# tetris_fs.net
KiCad netlist of a schematic drawn in EAGLE
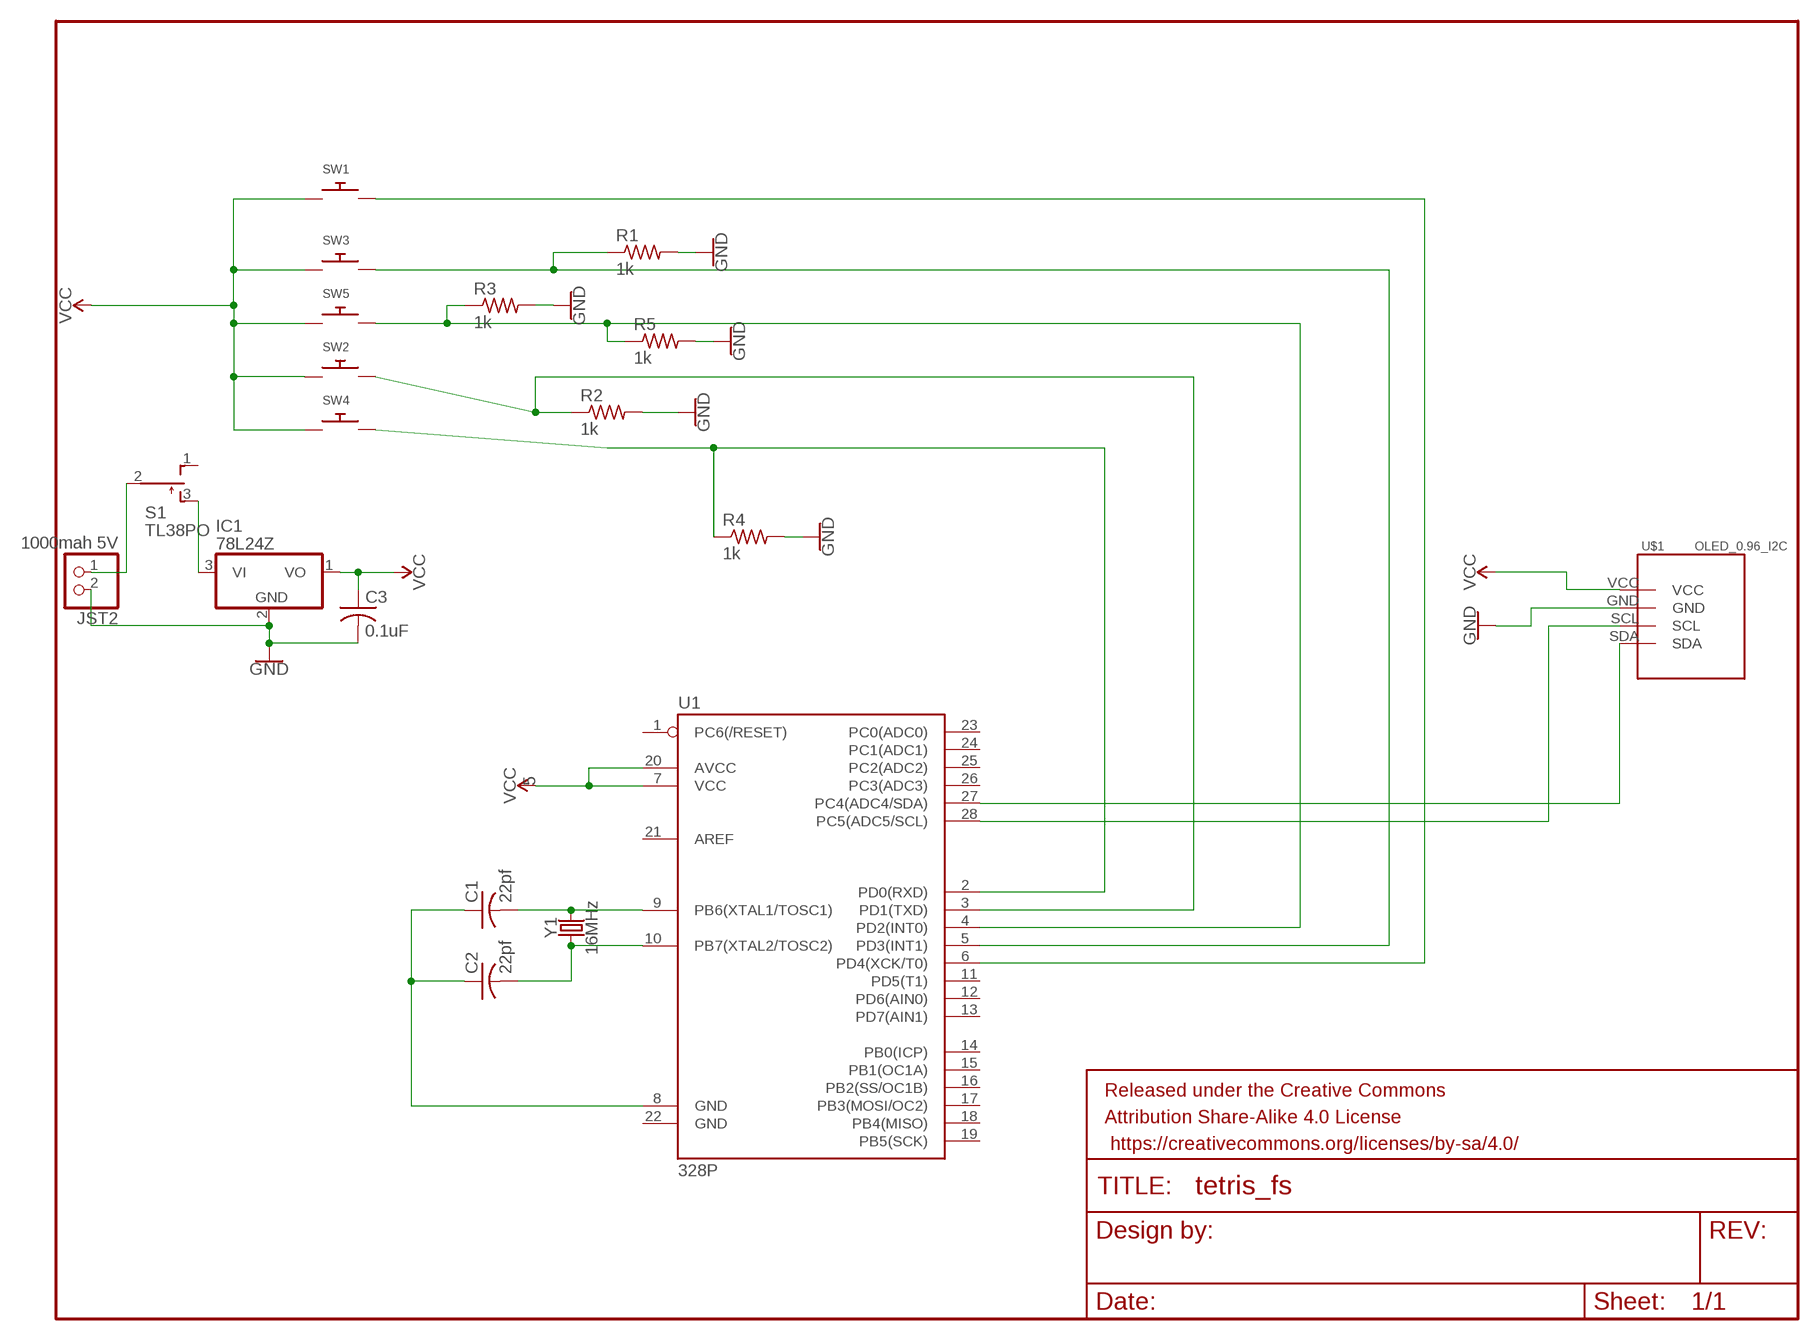
[diagram p0: schematic, sheet 1]

(export (version "E")
  (design (tool "Eeschema 10.0.6"))
  (components
    (comp (ref "C1")
      (value "22pf")
      (footprint "eagle-import:C050-030X075")
      (libsource (lib "eagle-import") (part "C-US050-030X075"))
    )
    (comp (ref "C2")
      (value "22pf")
      (footprint "eagle-import:C050-030X075")
      (libsource (lib "eagle-import") (part "C-US050-030X075"))
    )
    (comp (ref "C3")
      (value "0.1uF")
      (footprint "eagle-import:C050-030X075")
      (libsource (lib "eagle-import") (part "C-US050-030X075"))
    )
    (comp (ref "FRAME1")
      (value "FRAME-LETTERNO_PACKAGE")
      (footprint "eagle-import:DUMMY")
      (fields (field (name "DESIGNER") "Nobody"))
      (libsource (lib "eagle-import") (part "FRAME-LETTERNO_PACKAGE"))
    )
    (comp (ref "IC1")
      (value "78L24Z")
      (footprint "eagle-import:TO92")
      (libsource (lib "eagle-import") (part "78ZL24"))
    )
    (comp (ref "JST2")
      (value "1000mah 5V")
      (footprint "eagle-import:JST-PH-2-SMT-RA")
      (libsource (lib "eagle-import") (part "JST_2PIN-SMT-RA"))
    )
    (comp (ref "R1")
      (value "1k")
      (footprint "eagle-import:0805-THM")
      (libsource (lib "eagle-import") (part "R-US_FLIPFLOP"))
    )
    (comp (ref "R2")
      (value "1k")
      (footprint "eagle-import:0805-THM")
      (libsource (lib "eagle-import") (part "R-US_FLIPFLOP"))
    )
    (comp (ref "R3")
      (value "1k")
      (footprint "eagle-import:0805-THM")
      (libsource (lib "eagle-import") (part "R-US_FLIPFLOP"))
    )
    (comp (ref "R4")
      (value "1k")
      (footprint "eagle-import:0805-THM")
      (libsource (lib "eagle-import") (part "R-US_FLIPFLOP"))
    )
    (comp (ref "R5")
      (value "1k")
      (footprint "eagle-import:0805-THM")
      (libsource (lib "eagle-import") (part "R-US_FLIPFLOP"))
    )
    (comp (ref "S1")
      (value "TL38PO")
      (footprint "eagle-import:TL3XPO")
      (libsource (lib "eagle-import") (part "TL38PO"))
    )
    (comp (ref "SW1")
      (value "SWITCH_PUSHBUTTONC&K_KSS")
      (footprint "eagle-import:BTN_CK_KSS")
      (libsource (lib "eagle-import") (part "SWITCH_PUSHBUTTONC&K_KSS"))
    )
    (comp (ref "SW2")
      (value "SWITCH_PUSHBUTTONC&K_KSS")
      (footprint "eagle-import:BTN_CK_KSS")
      (libsource (lib "eagle-import") (part "SWITCH_PUSHBUTTONC&K_KSS"))
    )
    (comp (ref "SW3")
      (value "SWITCH_PUSHBUTTONC&K_KSS")
      (footprint "eagle-import:BTN_CK_KSS")
      (libsource (lib "eagle-import") (part "SWITCH_PUSHBUTTONC&K_KSS"))
    )
    (comp (ref "SW4")
      (value "SWITCH_PUSHBUTTONC&K_KSS")
      (footprint "eagle-import:BTN_CK_KSS")
      (libsource (lib "eagle-import") (part "SWITCH_PUSHBUTTONC&K_KSS"))
    )
    (comp (ref "SW5")
      (value "SWITCH_PUSHBUTTONC&K_KSS")
      (footprint "eagle-import:BTN_CK_KSS")
      (libsource (lib "eagle-import") (part "SWITCH_PUSHBUTTONC&K_KSS"))
    )
    (comp (ref "U$1")
      (value "OLED_0.96_I2C")
      (footprint "eagle-import:OLED_0.96_I2C")
      (libsource (lib "eagle-import") (part "OLED_0.96_I2C"))
    )
    (comp (ref "U1")
      (value "328P")
      (footprint "eagle-import:DIP28")
      (libsource (lib "eagle-import") (part "ATMEGA328P_PDIP"))
    )
    (comp (ref "Y1")
      (value "16MHz")
      (footprint "eagle-import:HC49US")
      (libsource (lib "eagle-import") (part "CRYSTAL-16MHZPTH-HC49US"))
    )
  )
  (nets
    (net (code "1") (name "GND") (class "Default")
      (node (ref "C3") (pin "2") (pinfunction "2_2") (pintype "passive"))
      (node (ref "IC1") (pin "2") (pinfunction "GND_2") (pintype "passive"))
      (node (ref "JST2") (pin "2") (pinfunction "1_2") (pintype "passive"))
      (node (ref "R1") (pin "2") (pinfunction "2_2") (pintype "passive"))
      (node (ref "R2") (pin "2") (pinfunction "2_2") (pintype "passive"))
      (node (ref "R3") (pin "2") (pinfunction "2_2") (pintype "passive"))
      (node (ref "R4") (pin "2") (pinfunction "2_2") (pintype "passive"))
      (node (ref "R5") (pin "2") (pinfunction "2_2") (pintype "passive"))
      (node (ref "U$1") (pin "GND") (pinfunction "GND_GND") (pintype "bidirectional"))
    )
    (net (code "2") (name "Net-(C1-Pad1)") (class "Default")
      (node (ref "C1") (pin "1") (pinfunction "1_1") (pintype "passive"))
      (node (ref "C2") (pin "1") (pinfunction "1_1") (pintype "passive"))
      (node (ref "U1") (pin "8") (pinfunction "GND_8") (pintype "bidirectional"))
    )
    (net (code "3") (name "Net-(IC1-VI)") (class "Default")
      (node (ref "IC1") (pin "3") (pinfunction "VI_3") (pintype "input"))
      (node (ref "S1") (pin "3") (pinfunction "S_3") (pintype "passive"))
    )
    (net (code "4") (name "Net-(JST2-2)") (class "Default")
      (node (ref "JST2") (pin "1") (pinfunction "2_1") (pintype "passive"))
      (node (ref "S1") (pin "2") (pinfunction "P_2") (pintype "passive"))
    )
    (net (code "5") (name "Net-(U1-PB6(XTAL1{slash}TOSC1))") (class "Default")
      (node (ref "C1") (pin "2") (pinfunction "2_2") (pintype "passive"))
      (node (ref "U1") (pin "9") (pinfunction "PB6(XTAL1/TOSC1)_9") (pintype "bidirectional"))
      (node (ref "Y1") (pin "2") (pinfunction "2_2") (pintype "passive"))
    )
    (net (code "6") (name "Net-(U1-PB7(XTAL2{slash}TOSC2))") (class "Default")
      (node (ref "C2") (pin "2") (pinfunction "2_2") (pintype "passive"))
      (node (ref "U1") (pin "10") (pinfunction "PB7(XTAL2/TOSC2)_10") (pintype "bidirectional"))
      (node (ref "Y1") (pin "1") (pinfunction "1_1") (pintype "passive"))
    )
    (net (code "7") (name "Net-(U1-PC4(ADC4{slash}SDA))") (class "Default")
      (node (ref "U$1") (pin "SDA") (pinfunction "SDA_SDA") (pintype "bidirectional"))
      (node (ref "U1") (pin "27") (pinfunction "PC4(ADC4/SDA)_27") (pintype "bidirectional"))
    )
    (net (code "8") (name "Net-(U1-PC5(ADC5{slash}SCL))") (class "Default")
      (node (ref "U$1") (pin "SCL") (pinfunction "SCL_SCL") (pintype "bidirectional"))
      (node (ref "U1") (pin "28") (pinfunction "PC5(ADC5/SCL)_28") (pintype "bidirectional"))
    )
    (net (code "9") (name "Net-(U1-PD0(RXD))") (class "Default")
      (node (ref "R4") (pin "1") (pinfunction "1_1") (pintype "passive"))
      (node (ref "SW4") (pin "P$2") (pinfunction "P$2_P$2") (pintype "passive"))
      (node (ref "U1") (pin "2") (pinfunction "PD0(RXD)_2") (pintype "bidirectional"))
    )
    (net (code "10") (name "Net-(U1-PD1(TXD))") (class "Default")
      (node (ref "R2") (pin "1") (pinfunction "1_1") (pintype "passive"))
      (node (ref "SW2") (pin "P$2") (pinfunction "P$2_P$2") (pintype "passive"))
      (node (ref "U1") (pin "3") (pinfunction "PD1(TXD)_3") (pintype "bidirectional"))
    )
    (net (code "11") (name "Net-(U1-PD2(INT0))") (class "Default")
      (node (ref "R3") (pin "1") (pinfunction "1_1") (pintype "passive"))
      (node (ref "R5") (pin "1") (pinfunction "1_1") (pintype "passive"))
      (node (ref "SW5") (pin "P$2") (pinfunction "P$2_P$2") (pintype "passive"))
      (node (ref "U1") (pin "4") (pinfunction "PD2(INT0)_4") (pintype "bidirectional"))
    )
    (net (code "12") (name "Net-(U1-PD3(INT1))") (class "Default")
      (node (ref "R1") (pin "1") (pinfunction "1_1") (pintype "passive"))
      (node (ref "SW3") (pin "P$2") (pinfunction "P$2_P$2") (pintype "passive"))
      (node (ref "U1") (pin "5") (pinfunction "PD3(INT1)_5") (pintype "bidirectional"))
    )
    (net (code "13") (name "Net-(U1-PD4(XCK{slash}T0))") (class "Default")
      (node (ref "SW1") (pin "P$2") (pinfunction "P$2_P$2") (pintype "passive"))
      (node (ref "U1") (pin "6") (pinfunction "PD4(XCK/T0)_6") (pintype "bidirectional"))
    )
    (net (code "14") (name "VCC") (class "Default")
      (node (ref "C3") (pin "1") (pinfunction "1_1") (pintype "passive"))
      (node (ref "IC1") (pin "1") (pinfunction "VO_1") (pintype "passive"))
      (node (ref "SW1") (pin "P$1") (pinfunction "P$1_P$1") (pintype "passive"))
      (node (ref "SW2") (pin "P$1") (pinfunction "P$1_P$1") (pintype "passive"))
      (node (ref "SW3") (pin "P$1") (pinfunction "P$1_P$1") (pintype "passive"))
      (node (ref "SW4") (pin "P$1") (pinfunction "P$1_P$1") (pintype "passive"))
      (node (ref "SW5") (pin "P$1") (pinfunction "P$1_P$1") (pintype "passive"))
      (node (ref "U$1") (pin "VCC") (pinfunction "VCC_VCC") (pintype "bidirectional"))
      (node (ref "U1") (pin "20") (pinfunction "AVCC_20") (pintype "bidirectional"))
      (node (ref "U1") (pin "7") (pinfunction "VCC_7") (pintype "bidirectional"))
    )
    (net (code "15") (name "unconnected-(S1-O-Pad1)") (class "Default")
      (node (ref "S1") (pin "1") (pinfunction "O_1") (pintype "passive"))
    )
    (net (code "16") (name "unconnected-(U1-AREF-Pad21)") (class "Default")
      (node (ref "U1") (pin "21") (pinfunction "AREF_21") (pintype "bidirectional"))
    )
    (net (code "17") (name "unconnected-(U1-GND-Pad22)") (class "Default")
      (node (ref "U1") (pin "22") (pinfunction "GND_22") (pintype "bidirectional"))
    )
    (net (code "18") (name "unconnected-(U1-PB0(ICP)-Pad14)") (class "Default")
      (node (ref "U1") (pin "14") (pinfunction "PB0(ICP)_14") (pintype "bidirectional"))
    )
    (net (code "19") (name "unconnected-(U1-PB1(OC1A)-Pad15)") (class "Default")
      (node (ref "U1") (pin "15") (pinfunction "PB1(OC1A)_15") (pintype "bidirectional"))
    )
    (net (code "20") (name "unconnected-(U1-PB2(SS{slash}OC1B)-Pad16)") (class "Default")
      (node (ref "U1") (pin "16") (pinfunction "PB2(SS/OC1B)_16") (pintype "bidirectional"))
    )
    (net (code "21") (name "unconnected-(U1-PB3(MOSI{slash}OC2)-Pad17)") (class "Default")
      (node (ref "U1") (pin "17") (pinfunction "PB3(MOSI/OC2)_17") (pintype "bidirectional"))
    )
    (net (code "22") (name "unconnected-(U1-PB4(MISO)-Pad18)") (class "Default")
      (node (ref "U1") (pin "18") (pinfunction "PB4(MISO)_18") (pintype "bidirectional"))
    )
    (net (code "23") (name "unconnected-(U1-PB5(SCK)-Pad19)") (class "Default")
      (node (ref "U1") (pin "19") (pinfunction "PB5(SCK)_19") (pintype "bidirectional"))
    )
    (net (code "24") (name "unconnected-(U1-PC0(ADC0)-Pad23)") (class "Default")
      (node (ref "U1") (pin "23") (pinfunction "PC0(ADC0)_23") (pintype "bidirectional"))
    )
    (net (code "25") (name "unconnected-(U1-PC1(ADC1)-Pad24)") (class "Default")
      (node (ref "U1") (pin "24") (pinfunction "PC1(ADC1)_24") (pintype "bidirectional"))
    )
    (net (code "26") (name "unconnected-(U1-PC2(ADC2)-Pad25)") (class "Default")
      (node (ref "U1") (pin "25") (pinfunction "PC2(ADC2)_25") (pintype "bidirectional"))
    )
    (net (code "27") (name "unconnected-(U1-PC3(ADC3)-Pad26)") (class "Default")
      (node (ref "U1") (pin "26") (pinfunction "PC3(ADC3)_26") (pintype "bidirectional"))
    )
    (net (code "28") (name "unconnected-(U1-PC6({slash}RESET)-Pad1)") (class "Default")
      (node (ref "U1") (pin "1") (pinfunction "PC6(/RESET)_1") (pintype "bidirectional"))
    )
    (net (code "29") (name "unconnected-(U1-PD5(T1)-Pad11)") (class "Default")
      (node (ref "U1") (pin "11") (pinfunction "PD5(T1)_11") (pintype "bidirectional"))
    )
    (net (code "30") (name "unconnected-(U1-PD6(AIN0)-Pad12)") (class "Default")
      (node (ref "U1") (pin "12") (pinfunction "PD6(AIN0)_12") (pintype "bidirectional"))
    )
    (net (code "31") (name "unconnected-(U1-PD7(AIN1)-Pad13)") (class "Default")
      (node (ref "U1") (pin "13") (pinfunction "PD7(AIN1)_13") (pintype "bidirectional"))
    )
  )
)
